# Power.net
KiCad netlist of a schematic drawn in Altium Designer
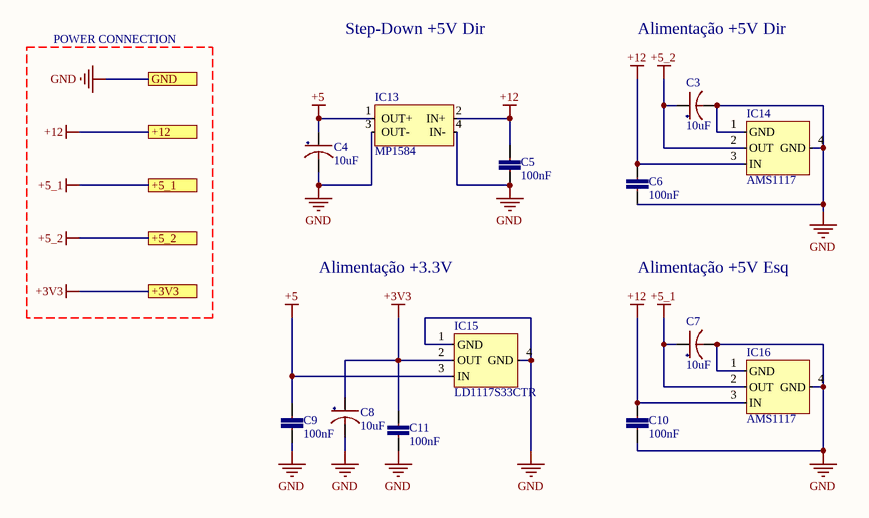
[diagram p0: Power.SchDoc]

(export (version "E")
  (design (tool "Eeschema 10.0.6"))
  (components
    (comp (ref "C3")
      (value "10uF")
      (footprint "CAP ALUM 5X5")
      (description "Aluminum Electrolytic Capacitors - SMD 25volts 10uF 5x5.4 20%")
      (fields (field (name "MFR") "Nichion"))
      (libsource (lib "") (part "CAP ALUM 25V 10uF_1"))
    )
    (comp (ref "C4")
      (value "10uF")
      (footprint "CAP ALUM 5X5")
      (description "Aluminum Electrolytic Capacitors - SMD 25volts 10uF 5x5.4 20%")
      (fields (field (name "MFR") "Nichion"))
      (libsource (lib "Schlib-Placa-Mae") (part "CAP ALUM 25V 10uF"))
    )
    (comp (ref "C5")
      (value "100nF")
      (footprint "CAP CER 0603")
      (description "Multilayer Ceramic Capacitors MLCC - SMD/SMT 25V 0.1uF 0603 Y5V -20/+80%")
      (fields (field (name "MFR") "KEMET"))
      (libsource (lib "Schlib-Placa-Mae") (part "CAP CER 0603 25V 100nF"))
    )
    (comp (ref "C6")
      (value "100nF")
      (footprint "CAP CER 0603")
      (description "Multilayer Ceramic Capacitors MLCC - SMD/SMT 25V 0.1uF 0603 Y5V -20/+80%")
      (fields (field (name "MFR") "KEMET"))
      (libsource (lib "Schlib-Placa-Mae") (part "CAP CER 0603 25V 100nF"))
    )
    (comp (ref "C7")
      (value "10uF")
      (footprint "CAP ALUM 5X5")
      (description "Aluminum Electrolytic Capacitors - SMD 25volts 10uF 5x5.4 20%")
      (fields (field (name "MFR") "Nichion"))
      (libsource (lib "") (part "CAP ALUM 25V 10uF_1"))
    )
    (comp (ref "C8")
      (value "10uF")
      (footprint "CAP ALUM 5X5")
      (description "Aluminum Electrolytic Capacitors - SMD 25volts 10uF 5x5.4 20%")
      (fields (field (name "MFR") "Nichion"))
      (libsource (lib "Schlib-Placa-Mae") (part "CAP ALUM 25V 10uF"))
    )
    (comp (ref "C9")
      (value "100nF")
      (footprint "CAP CER 0603")
      (description "Multilayer Ceramic Capacitors MLCC - SMD/SMT 25V 0.1uF 0603 Y5V -20/+80%")
      (fields (field (name "MFR") "KEMET"))
      (libsource (lib "Schlib-Placa-Mae") (part "CAP CER 0603 25V 100nF"))
    )
    (comp (ref "C10")
      (value "100nF")
      (footprint "CAP CER 0603")
      (description "Multilayer Ceramic Capacitors MLCC - SMD/SMT 25V 0.1uF 0603 Y5V -20/+80%")
      (fields (field (name "MFR") "KEMET"))
      (libsource (lib "Schlib-Placa-Mae") (part "CAP CER 0603 25V 100nF"))
    )
    (comp (ref "C11")
      (value "100nF")
      (footprint "CAP CER 0603")
      (description "Multilayer Ceramic Capacitors MLCC - SMD/SMT 25V 0.1uF 0603 Y5V -20/+80%")
      (fields (field (name "MFR") "KEMET"))
      (libsource (lib "Schlib-Placa-Mae") (part "CAP CER 0603 25V 100nF"))
    )
    (comp (ref "IC13")
      (value "MP1584")
      (footprint "MP1584")
      (libsource (lib "Schlib-Placa-Mae") (part "MP1584"))
    )
    (comp (ref "IC14")
      (value "AMS1117")
      (footprint "SOT-223")
      (description "LDO Voltage Regulators 5V 1A")
      (fields (field (name "MFR") "STMicroelectronics"))
      (libsource (lib "Schlib-Placa-Mae") (part "AMS1117"))
    )
    (comp (ref "IC15")
      (value "LD1117S33CTR")
      (footprint "SOT-223")
      (description "LDO Voltage Regulators 3.3V 0.8A Positive")
      (fields (field (name "MFR") "STMicroelectronics"))
      (libsource (lib "Schlib-Placa-Mae") (part "LD1117S33CTR"))
    )
    (comp (ref "IC16")
      (value "AMS1117")
      (footprint "SOT-223")
      (description "LDO Voltage Regulators 5V 1A")
      (fields (field (name "MFR") "STMicroelectronics"))
      (libsource (lib "Schlib-Placa-Mae") (part "AMS1117"))
    )
  )
  (nets
    (net (code "1") (name "+3V3") (class "Default")
      (node (ref "C11") (pin "2") (pinfunction "2_2") (pintype "passive"))
      (node (ref "C8") (pin "1") (pinfunction "1_1") (pintype "passive"))
      (node (ref "IC15") (pin "2") (pinfunction "OUT_2") (pintype "passive"))
    )
    (net (code "2") (name "+5") (class "Default")
      (node (ref "C4") (pin "1") (pinfunction "1_1") (pintype "passive"))
      (node (ref "C9") (pin "2") (pinfunction "2_2") (pintype "passive"))
      (node (ref "IC13") (pin "1") (pinfunction "OUT+_1") (pintype "passive"))
      (node (ref "IC15") (pin "3") (pinfunction "IN_3") (pintype "passive"))
    )
    (net (code "3") (name "+5_1") (class "Default")
      (node (ref "C7") (pin "1") (pinfunction "1_1") (pintype "passive"))
      (node (ref "IC16") (pin "2") (pinfunction "OUT_2") (pintype "passive"))
    )
    (net (code "4") (name "+5_2") (class "Default")
      (node (ref "C3") (pin "1") (pinfunction "1_1") (pintype "passive"))
      (node (ref "IC14") (pin "2") (pinfunction "OUT_2") (pintype "passive"))
    )
    (net (code "5") (name "+12") (class "Default")
      (node (ref "C10") (pin "2") (pinfunction "2_2") (pintype "passive"))
      (node (ref "C5") (pin "2") (pinfunction "2_2") (pintype "passive"))
      (node (ref "C6") (pin "2") (pinfunction "2_2") (pintype "passive"))
      (node (ref "IC13") (pin "2") (pinfunction "IN+_2") (pintype "passive"))
      (node (ref "IC14") (pin "3") (pinfunction "IN_3") (pintype "passive"))
      (node (ref "IC16") (pin "3") (pinfunction "IN_3") (pintype "passive"))
    )
    (net (code "6") (name "GND") (class "Default")
      (node (ref "C10") (pin "1") (pinfunction "1_1") (pintype "passive"))
      (node (ref "C11") (pin "1") (pinfunction "1_1") (pintype "passive"))
      (node (ref "C3") (pin "2") (pinfunction "2_2") (pintype "passive"))
      (node (ref "C4") (pin "2") (pinfunction "2_2") (pintype "passive"))
      (node (ref "C5") (pin "1") (pinfunction "1_1") (pintype "passive"))
      (node (ref "C6") (pin "1") (pinfunction "1_1") (pintype "passive"))
      (node (ref "C7") (pin "2") (pinfunction "2_2") (pintype "passive"))
      (node (ref "C8") (pin "2") (pinfunction "2_2") (pintype "passive"))
      (node (ref "C9") (pin "1") (pinfunction "1_1") (pintype "passive"))
      (node (ref "IC13") (pin "3") (pinfunction "OUT-_3") (pintype "passive"))
      (node (ref "IC13") (pin "4") (pinfunction "IN-_4") (pintype "passive"))
      (node (ref "IC14") (pin "1") (pinfunction "GND_1") (pintype "passive"))
      (node (ref "IC14") (pin "4") (pinfunction "GND_4") (pintype "passive"))
      (node (ref "IC15") (pin "1") (pinfunction "GND_1") (pintype "passive"))
      (node (ref "IC15") (pin "4") (pinfunction "GND_4") (pintype "passive"))
      (node (ref "IC16") (pin "1") (pinfunction "GND_1") (pintype "passive"))
      (node (ref "IC16") (pin "4") (pinfunction "GND_4") (pintype "passive"))
    )
  )
)
